# mine.net
KiCad netlist of a schematic drawn in EasyEDA Pro
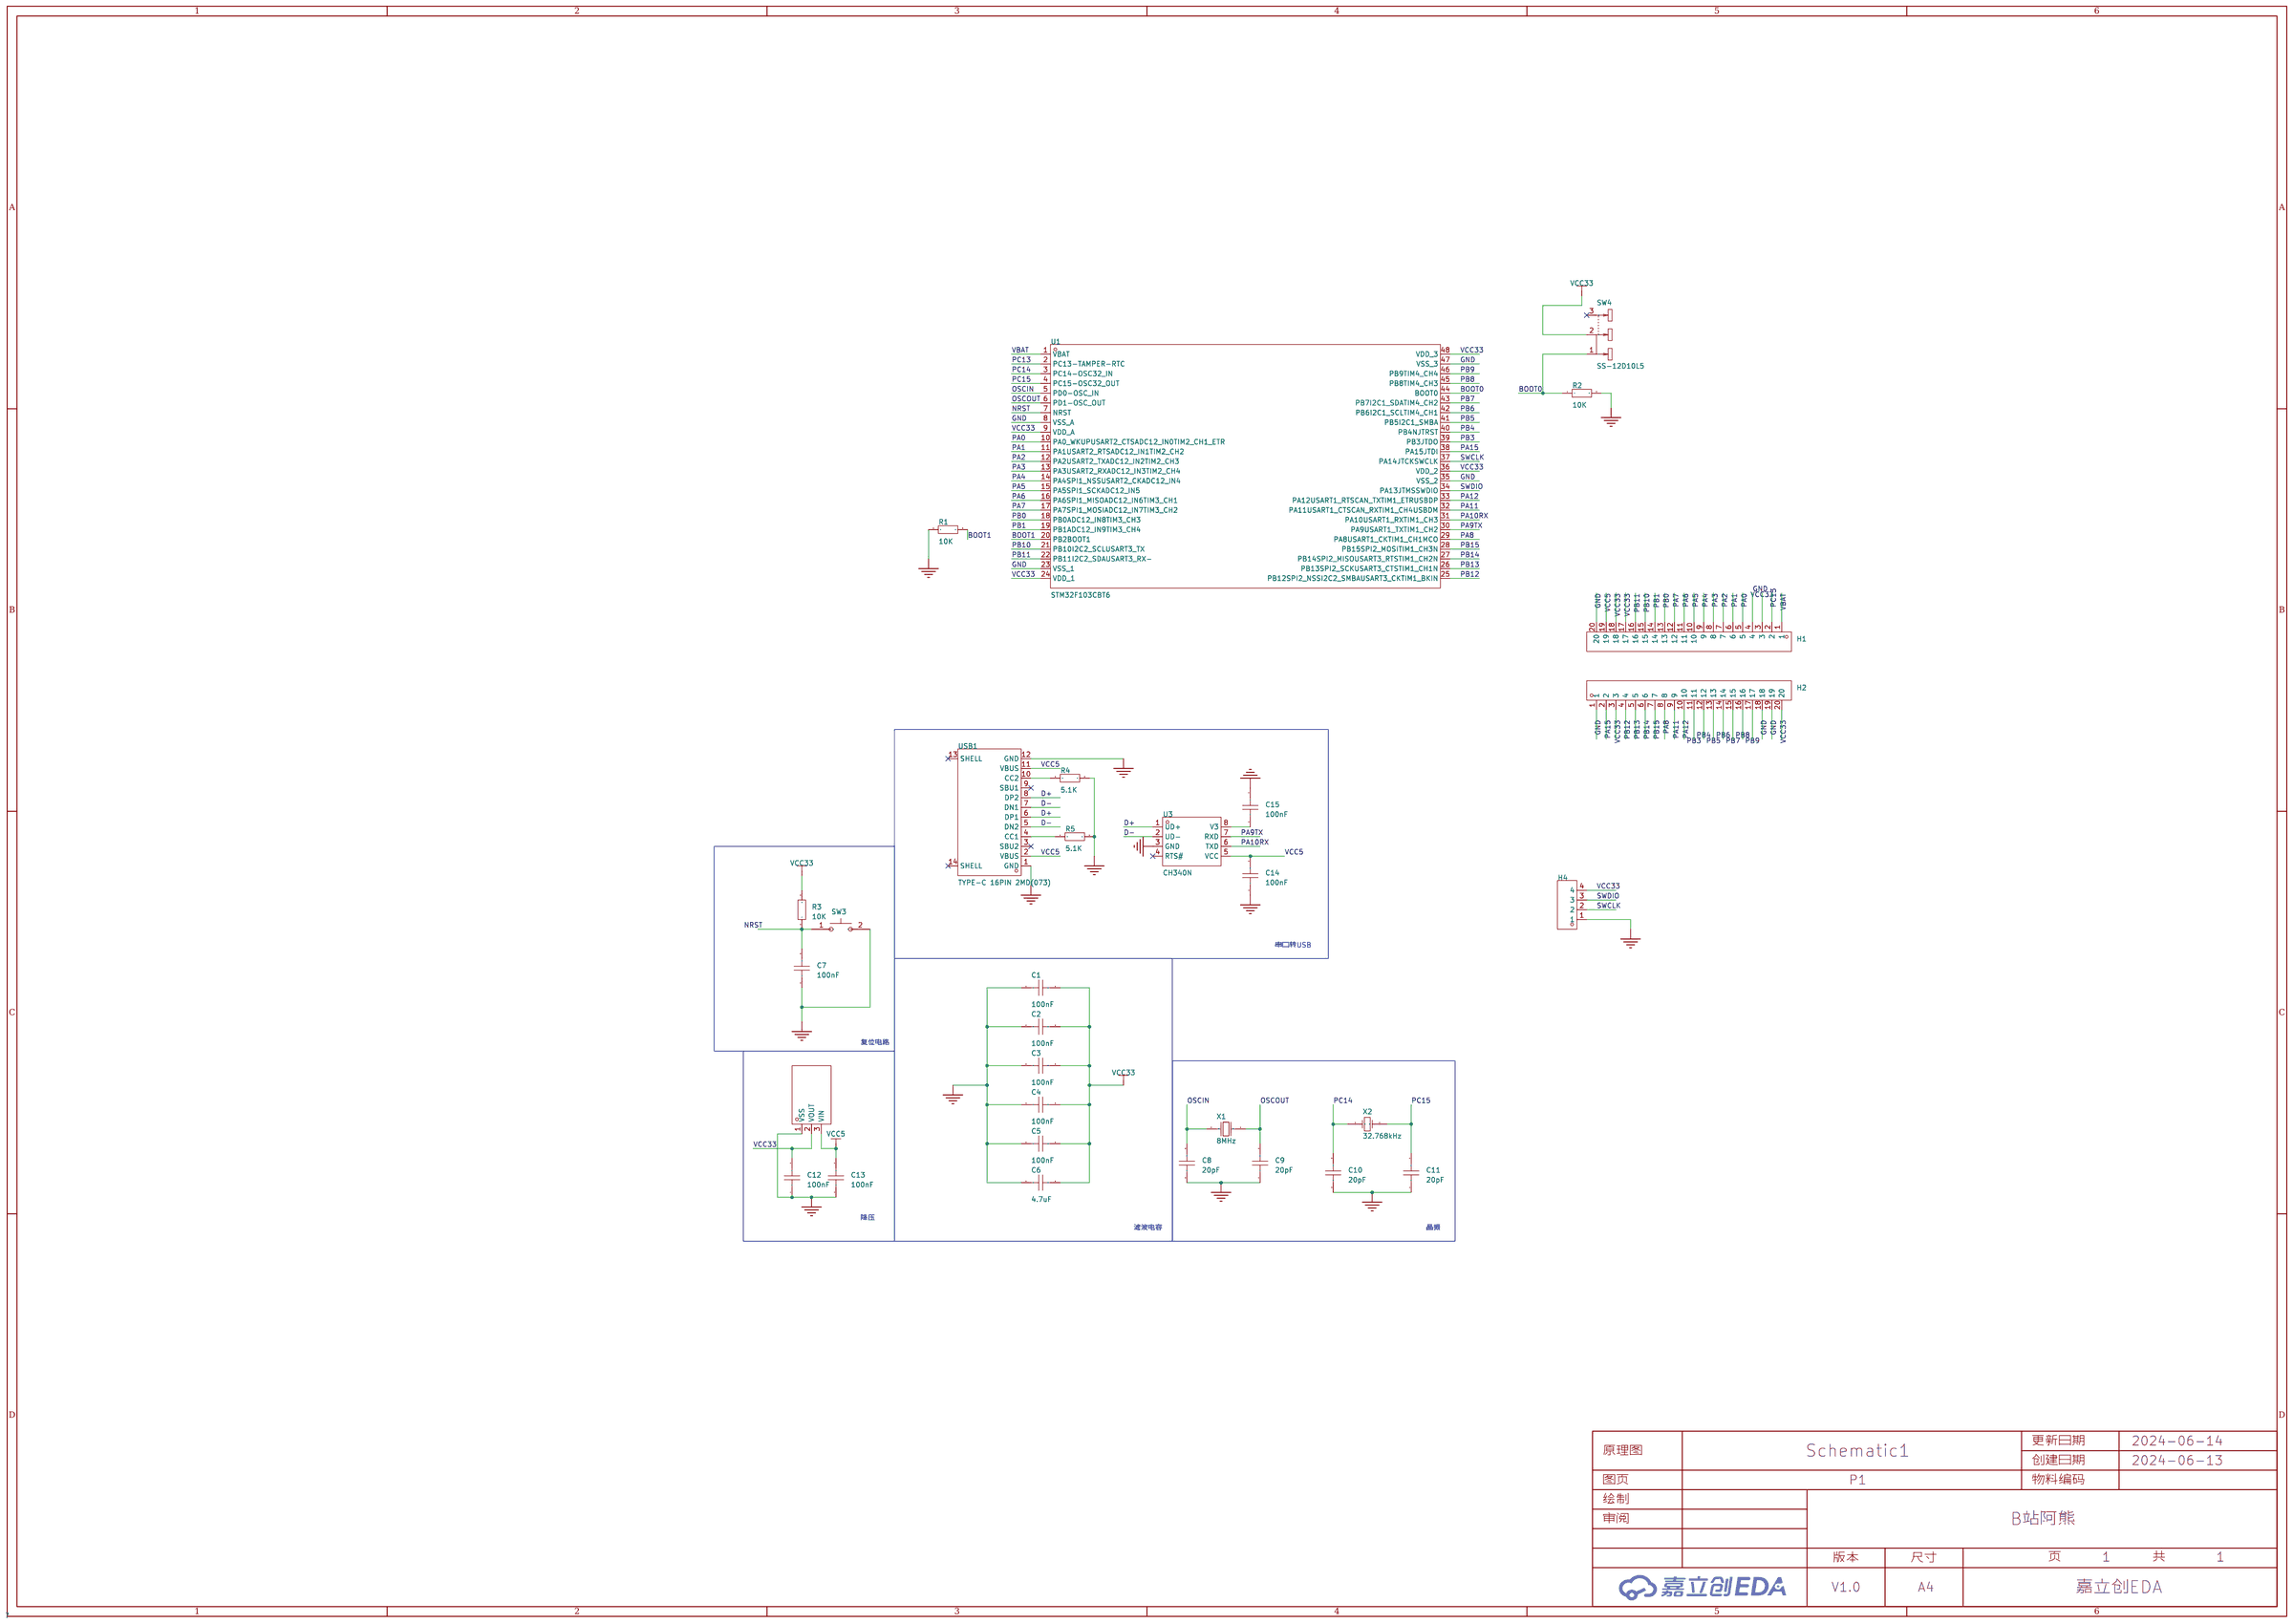
[diagram p0: schematic sheet]

(export (version "E")
  (design (tool "Eeschema 10.0.6"))
  (components
    (comp (ref "C1")
      (value "100nF")
      (footprint "easyedapro:C0603")
      (libsource (lib "easyedapro") (part "CapAcitance"))
    )
    (comp (ref "C2")
      (value "100nF")
      (footprint "easyedapro:C0603")
      (libsource (lib "easyedapro") (part "CapAcitance"))
    )
    (comp (ref "C3")
      (value "100nF")
      (footprint "easyedapro:C0603")
      (libsource (lib "easyedapro") (part "CapAcitance"))
    )
    (comp (ref "C4")
      (value "100nF")
      (footprint "easyedapro:C0603")
      (libsource (lib "easyedapro") (part "CapAcitance"))
    )
    (comp (ref "C5")
      (value "100nF")
      (footprint "easyedapro:C0603")
      (libsource (lib "easyedapro") (part "CapAcitance"))
    )
    (comp (ref "C6")
      (value "4.7uF")
      (footprint "easyedapro:C0603")
      (libsource (lib "easyedapro") (part "CapAcitance"))
    )
    (comp (ref "C7")
      (value "100nF")
      (footprint "easyedapro:C0603")
      (libsource (lib "easyedapro") (part "CapAcitance"))
    )
    (comp (ref "C8")
      (value "20pF")
      (footprint "easyedapro:C0603")
      (libsource (lib "easyedapro") (part "CapAcitance"))
    )
    (comp (ref "C9")
      (value "20pF")
      (footprint "easyedapro:C0603")
      (libsource (lib "easyedapro") (part "CapAcitance"))
    )
    (comp (ref "C10")
      (value "20pF")
      (footprint "easyedapro:C0603")
      (libsource (lib "easyedapro") (part "CapAcitance"))
    )
    (comp (ref "C11")
      (value "20pF")
      (footprint "easyedapro:C0603")
      (libsource (lib "easyedapro") (part "CapAcitance"))
    )
    (comp (ref "C12")
      (value "100nF")
      (footprint "easyedapro:C0603")
      (libsource (lib "easyedapro") (part "CapAcitance"))
    )
    (comp (ref "C13")
      (value "100nF")
      (footprint "easyedapro:C0603")
      (libsource (lib "easyedapro") (part "CapAcitance"))
    )
    (comp (ref "C14")
      (value "100nF")
      (footprint "easyedapro:C0603")
      (libsource (lib "easyedapro") (part "CapAcitance"))
    )
    (comp (ref "C15")
      (value "100nF")
      (footprint "easyedapro:C0603")
      (libsource (lib "easyedapro") (part "CapAcitance"))
    )
    (comp (ref "H1")
      (value "~")
      (footprint "easyedapro:HDR-TH_20P-P2.54-V-M-1")
      (libsource (lib "easyedapro") (part "HDR_2.54-1x20P"))
    )
    (comp (ref "H2")
      (value "~")
      (footprint "easyedapro:HDR-TH_20P-P2.54-V-M-1")
      (libsource (lib "easyedapro") (part "HDR_2.54-1x20P"))
    )
    (comp (ref "H4")
      (value "~")
      (footprint "easyedapro:HDR-TH_4P-P2.54-V-M")
      (libsource (lib "easyedapro") (part "PZ254V-11-04P"))
    )
    (comp (ref "R1") (value "10K") (footprint "easyedapro:R0603") (libsource (lib "easyedapro") (part "电阻")))
    (comp (ref "R2") (value "10K") (footprint "easyedapro:R0603") (libsource (lib "easyedapro") (part "电阻")))
    (comp (ref "R3") (value "10K") (footprint "easyedapro:R0603") (libsource (lib "easyedapro") (part "电阻")))
    (comp (ref "R4") (value "5.1K") (footprint "easyedapro:R0603") (libsource (lib "easyedapro") (part "电阻")))
    (comp (ref "R5") (value "5.1K") (footprint "easyedapro:R0603") (libsource (lib "easyedapro") (part "电阻")))
    (comp (ref "SW3")
      (value "1TS002C-2300-4300-CT")
      (footprint "easyedapro:SW-SMD_L6.0-W3.5-LS8.0-EH")
      (fields (field (name "Manufacturer") "HYP(鸿源精密)"))
      (libsource (lib "easyedapro") (part "1TS002C-2300-4300"))
    )
    (comp (ref "SW4")
      (value "SS-12D10L5")
      (footprint "easyedapro:SW-TH_SS-12D10L5")
      (description "电路结构:单刀双掷;安装方式:直插;开关颜色:黑色;额定电流(DC):3A;额定电压(DC):125V;额定电流(AC):3A;额定电压(AC):125V;机械寿命:1万次;")
      (fields (field (name "Manufacturer") "XKB Connectivity(中国星坤)"))
      (libsource (lib "easyedapro") (part "SS-12D10L5"))
    )
    (comp (ref "U1")
      (value "STM32F103CBT6")
      (footprint "easyedapro:LQFP-48_L7.0-W7.0-P0.50-LS9.0-BL")
      (description "CPU内核:CM3;程序存储容量:128KB;RAM总容量:20KB;GPIO端口数量:37;工作电压范围:2V~3.6V;CPU最大主频:72MHz;程序存储器类型:FLASH;")
      (fields (field (name "Manufacturer") "ST(意法半导体)"))
      (libsource (lib "easyedapro") (part "STM32F103CBT6"))
    )
    (comp (ref "U2")
      (value "ME6206A33XG")
      (footprint "easyedapro:SOT-23-3_L2.9-W1.6-P1.90-LS2.8-BR")
      (description "输出类型:固定;最大输入电压:6V;输出电压:3.3V;最大输出电流:300mA;电源纹波抑制比(PSRR):50dB@(1kHz);输出极性:正极;")
      (fields (field (name "Manufacturer") "MICRONE(南京微盟)"))
      (libsource (lib "easyedapro") (part "ME6206A33XG"))
    )
    (comp (ref "U3")
      (value "CH340N")
      (footprint "easyedapro:SOP-8_L4.9-W3.9-P1.27-LS6.0-BL")
      (fields (field (name "Manufacturer") "WCH(南京沁恒)"))
      (libsource (lib "easyedapro") (part "CH340N_C2977777"))
    )
    (comp (ref "USB1")
      (value "TYPE-C 16PIN 2MD(073)")
      (footprint "easyedapro:USB-C-SMD_TYPE-C-6PIN-2MD-073")
      (description "连接器类型:Type-C;标准:-;公母:母;端口数量:1;触点数量:16P;安装方式:卧贴;额定电流 - 电源:5A;工作温度范围:-25°C~+85°C;")
      (fields (field (name "Manufacturer") "SHOU HAN(首韩)"))
      (libsource (lib "easyedapro") (part "TYPE-C 16PIN 2MD(073)"))
    )
    (comp (ref "X1")
      (value "8MHz")
      (footprint "easyedapro:CRYSTAL-SMD_L11.5-W4.8-LS12.7")
      (description "晶振类型:贴片晶振;频率:8MHz;常温频差:±20ppm;外接负载电容:20pF;频率稳定度(全温):±30ppm;")
      (fields (field (name "Manufacturer Part") "X49SM8MSD2SC") (field (name "Manufacturer") "YXC(扬兴晶振)"))
      (libsource (lib "easyedapro") (part "X49SM8MSD2SC"))
    )
    (comp (ref "X2")
      (value "32.768kHz")
      (footprint "easyedapro:OSC-TH_BD3.1-P0.8-D0.3")
      (description "晶振类型:直插晶振;频率:32.768kHz;常温频差:±10ppm;外接负载电容:12.5pF;频率稳定度(全温):-;")
      (fields (field (name "Manufacturer Part") "X308032768KGB2SC") (field (name "Manufacturer") "YXC(扬兴晶振)"))
      (libsource (lib "easyedapro") (part "X308032768KGB2SC"))
    )
  )
  (nets
    (net (code "1") (name "/BOOT0") (class "Default")
      (node (ref "R2") (pin "1") (pinfunction "1_1") (pintype "input"))
      (node (ref "SW4") (pin "1") (pinfunction "1_1") (pintype "unspecified"))
      (node (ref "U1") (pin "44") (pinfunction "BOOT0_44") (pintype "unspecified"))
    )
    (net (code "2") (name "/BOOT1") (class "Default")
      (node (ref "R1") (pin "2") (pinfunction "2_2") (pintype "input"))
      (node (ref "U1") (pin "20") (pinfunction "PB2BOOT1_20") (pintype "unspecified"))
    )
    (net (code "3") (name "/D+") (class "Default")
      (node (ref "U3") (pin "1") (pinfunction "UD+_1") (pintype "unspecified"))
      (node (ref "USB1") (pin "6") (pinfunction "DP1_6") (pintype "unspecified"))
      (node (ref "USB1") (pin "8") (pinfunction "DP2_8") (pintype "unspecified"))
    )
    (net (code "4") (name "/D-") (class "Default")
      (node (ref "U3") (pin "2") (pinfunction "UD-_2") (pintype "unspecified"))
      (node (ref "USB1") (pin "5") (pinfunction "DN2_5") (pintype "unspecified"))
      (node (ref "USB1") (pin "7") (pinfunction "DN1_7") (pintype "unspecified"))
    )
    (net (code "5") (name "/NRST") (class "Default")
      (node (ref "C7") (pin "2") (pinfunction "2_2") (pintype "input"))
      (node (ref "R3") (pin "1") (pinfunction "1_1") (pintype "input"))
      (node (ref "SW3") (pin "1") (pinfunction "A_1") (pintype "input"))
      (node (ref "U1") (pin "7") (pinfunction "NRST_7") (pintype "unspecified"))
    )
    (net (code "6") (name "/OSCIN") (class "Default")
      (node (ref "C8") (pin "2") (pinfunction "2_2") (pintype "input"))
      (node (ref "U1") (pin "5") (pinfunction "PD0-OSC_IN_5") (pintype "unspecified"))
      (node (ref "X1") (pin "2") (pinfunction "OSC2_2") (pintype "input"))
    )
    (net (code "7") (name "/OSCOUT") (class "Default")
      (node (ref "C9") (pin "2") (pinfunction "2_2") (pintype "input"))
      (node (ref "U1") (pin "6") (pinfunction "PD1-OSC_OUT_6") (pintype "unspecified"))
      (node (ref "X1") (pin "1") (pinfunction "OSC1_1") (pintype "input"))
    )
    (net (code "8") (name "/PA0") (class "Default")
      (node (ref "H1") (pin "5") (pinfunction "5_5") (pintype "input"))
      (node (ref "U1") (pin "10") (pinfunction "PA0_WKUPUSART2_CTSADC12_IN0TIM2_CH1_ETR_10") (pintype "unspecified"))
    )
    (net (code "9") (name "/PA1") (class "Default")
      (node (ref "H1") (pin "6") (pinfunction "6_6") (pintype "input"))
      (node (ref "U1") (pin "11") (pinfunction "PA1USART2_RTSADC12_IN1TIM2_CH2_11") (pintype "unspecified"))
    )
    (net (code "10") (name "/PA2") (class "Default")
      (node (ref "H1") (pin "7") (pinfunction "7_7") (pintype "input"))
      (node (ref "U1") (pin "12") (pinfunction "PA2USART2_TXADC12_IN2TIM2_CH3_12") (pintype "unspecified"))
    )
    (net (code "11") (name "/PA3") (class "Default")
      (node (ref "H1") (pin "8") (pinfunction "8_8") (pintype "input"))
      (node (ref "U1") (pin "13") (pinfunction "PA3USART2_RXADC12_IN3TIM2_CH4_13") (pintype "unspecified"))
    )
    (net (code "12") (name "/PA4") (class "Default")
      (node (ref "H1") (pin "9") (pinfunction "9_9") (pintype "input"))
      (node (ref "U1") (pin "14") (pinfunction "PA4SPI1_NSSUSART2_CKADC12_IN4_14") (pintype "unspecified"))
    )
    (net (code "13") (name "/PA5") (class "Default")
      (node (ref "H1") (pin "10") (pinfunction "10_10") (pintype "input"))
      (node (ref "U1") (pin "15") (pinfunction "PA5SPI1_SCKADC12_IN5_15") (pintype "unspecified"))
    )
    (net (code "14") (name "/PA6") (class "Default")
      (node (ref "H1") (pin "11") (pinfunction "11_11") (pintype "input"))
      (node (ref "U1") (pin "16") (pinfunction "PA6SPI1_MISOADC12_IN6TIM3_CH1_16") (pintype "unspecified"))
    )
    (net (code "15") (name "/PA7") (class "Default")
      (node (ref "H1") (pin "12") (pinfunction "12_12") (pintype "input"))
      (node (ref "U1") (pin "17") (pinfunction "PA7SPI1_MOSIADC12_IN7TIM3_CH2_17") (pintype "unspecified"))
    )
    (net (code "16") (name "/PA8") (class "Default")
      (node (ref "H2") (pin "8") (pinfunction "8_8") (pintype "input"))
      (node (ref "U1") (pin "29") (pinfunction "PA8USART1_CKTIM1_CH1MCO_29") (pintype "unspecified"))
    )
    (net (code "17") (name "/PA9TX") (class "Default")
      (node (ref "U1") (pin "30") (pinfunction "PA9USART1_TXTIM1_CH2_30") (pintype "unspecified"))
      (node (ref "U3") (pin "7") (pinfunction "RXD_7") (pintype "unspecified"))
    )
    (net (code "18") (name "/PA10RX") (class "Default")
      (node (ref "U1") (pin "31") (pinfunction "PA10USART1_RXTIM1_CH3_31") (pintype "unspecified"))
      (node (ref "U3") (pin "6") (pinfunction "TXD_6") (pintype "unspecified"))
    )
    (net (code "19") (name "/PA11") (class "Default")
      (node (ref "H2") (pin "9") (pinfunction "9_9") (pintype "input"))
      (node (ref "U1") (pin "32") (pinfunction "PA11USART1_CTSCAN_RXTIM1_CH4USBDM_32") (pintype "unspecified"))
    )
    (net (code "20") (name "/PA12") (class "Default")
      (node (ref "H2") (pin "10") (pinfunction "10_10") (pintype "input"))
      (node (ref "U1") (pin "33") (pinfunction "PA12USART1_RTSCAN_TXTIM1_ETRUSBDP_33") (pintype "unspecified"))
    )
    (net (code "21") (name "/PA15") (class "Default")
      (node (ref "H2") (pin "2") (pinfunction "2_2") (pintype "input"))
      (node (ref "U1") (pin "38") (pinfunction "PA15JTDI_38") (pintype "unspecified"))
    )
    (net (code "22") (name "/PB0") (class "Default")
      (node (ref "H1") (pin "13") (pinfunction "13_13") (pintype "input"))
      (node (ref "U1") (pin "18") (pinfunction "PB0ADC12_IN8TIM3_CH3_18") (pintype "unspecified"))
    )
    (net (code "23") (name "/PB1") (class "Default")
      (node (ref "H1") (pin "14") (pinfunction "14_14") (pintype "input"))
      (node (ref "U1") (pin "19") (pinfunction "PB1ADC12_IN9TIM3_CH4_19") (pintype "unspecified"))
    )
    (net (code "24") (name "/PB3") (class "Default")
      (node (ref "H2") (pin "11") (pinfunction "11_11") (pintype "input"))
      (node (ref "U1") (pin "39") (pinfunction "PB3JTDO_39") (pintype "unspecified"))
    )
    (net (code "25") (name "/PB4") (class "Default")
      (node (ref "H2") (pin "12") (pinfunction "12_12") (pintype "input"))
      (node (ref "U1") (pin "40") (pinfunction "PB4NJTRST_40") (pintype "unspecified"))
    )
    (net (code "26") (name "/PB5") (class "Default")
      (node (ref "H2") (pin "13") (pinfunction "13_13") (pintype "input"))
      (node (ref "U1") (pin "41") (pinfunction "PB5I2C1_SMBA_41") (pintype "unspecified"))
    )
    (net (code "27") (name "/PB6") (class "Default")
      (node (ref "H2") (pin "14") (pinfunction "14_14") (pintype "input"))
      (node (ref "U1") (pin "42") (pinfunction "PB6I2C1_SCLTIM4_CH1_42") (pintype "unspecified"))
    )
    (net (code "28") (name "/PB7") (class "Default")
      (node (ref "H2") (pin "15") (pinfunction "15_15") (pintype "input"))
      (node (ref "U1") (pin "43") (pinfunction "PB7I2C1_SDATIM4_CH2_43") (pintype "unspecified"))
    )
    (net (code "29") (name "/PB8") (class "Default")
      (node (ref "H2") (pin "16") (pinfunction "16_16") (pintype "input"))
      (node (ref "U1") (pin "45") (pinfunction "PB8TIM4_CH3_45") (pintype "unspecified"))
    )
    (net (code "30") (name "/PB9") (class "Default")
      (node (ref "H2") (pin "17") (pinfunction "17_17") (pintype "input"))
      (node (ref "U1") (pin "46") (pinfunction "PB9TIM4_CH4_46") (pintype "unspecified"))
    )
    (net (code "31") (name "/PB10") (class "Default")
      (node (ref "H1") (pin "15") (pinfunction "15_15") (pintype "input"))
      (node (ref "U1") (pin "21") (pinfunction "PB10I2C2_SCLUSART3_TX_21") (pintype "unspecified"))
    )
    (net (code "32") (name "/PB11") (class "Default")
      (node (ref "H1") (pin "16") (pinfunction "16_16") (pintype "input"))
      (node (ref "U1") (pin "22") (pinfunction "PB11I2C2_SDAUSART3_RX-_22") (pintype "unspecified"))
    )
    (net (code "33") (name "/PB12") (class "Default")
      (node (ref "H2") (pin "4") (pinfunction "4_4") (pintype "input"))
      (node (ref "U1") (pin "25") (pinfunction "PB12SPI2_NSSI2C2_SMBAUSART3_CKTIM1_BKIN_25") (pintype "unspecified"))
    )
    (net (code "34") (name "/PB13") (class "Default")
      (node (ref "H2") (pin "5") (pinfunction "5_5") (pintype "input"))
      (node (ref "U1") (pin "26") (pinfunction "PB13SPI2_SCKUSART3_CTSTIM1_CH1N_26") (pintype "unspecified"))
    )
    (net (code "35") (name "/PB14") (class "Default")
      (node (ref "H2") (pin "6") (pinfunction "6_6") (pintype "input"))
      (node (ref "U1") (pin "27") (pinfunction "PB14SPI2_MISOUSART3_RTSTIM1_CH2N_27") (pintype "unspecified"))
    )
    (net (code "36") (name "/PB15") (class "Default")
      (node (ref "H2") (pin "7") (pinfunction "7_7") (pintype "input"))
      (node (ref "U1") (pin "28") (pinfunction "PB15SPI2_MOSITIM1_CH3N_28") (pintype "unspecified"))
    )
    (net (code "37") (name "/PC13") (class "Default")
      (node (ref "H1") (pin "2") (pinfunction "2_2") (pintype "input"))
      (node (ref "U1") (pin "2") (pinfunction "PC13-TAMPER-RTC_2") (pintype "unspecified"))
    )
    (net (code "38") (name "/PC14") (class "Default")
      (node (ref "C10") (pin "2") (pinfunction "2_2") (pintype "input"))
      (node (ref "U1") (pin "3") (pinfunction "PC14-OSC32_IN_3") (pintype "unspecified"))
      (node (ref "X2") (pin "1") (pinfunction "OSC1_1") (pintype "unspecified"))
    )
    (net (code "39") (name "/PC15") (class "Default")
      (node (ref "C11") (pin "2") (pinfunction "2_2") (pintype "input"))
      (node (ref "U1") (pin "4") (pinfunction "PC15-OSC32_OUT_4") (pintype "unspecified"))
      (node (ref "X2") (pin "2") (pinfunction "OSC2_2") (pintype "unspecified"))
    )
    (net (code "40") (name "/SWCLK") (class "Default")
      (node (ref "H4") (pin "2") (pinfunction "2_2") (pintype "unspecified"))
      (node (ref "U1") (pin "37") (pinfunction "PA14JTCKSWCLK_37") (pintype "unspecified"))
    )
    (net (code "41") (name "/SWDIO") (class "Default")
      (node (ref "H4") (pin "3") (pinfunction "3_3") (pintype "unspecified"))
      (node (ref "U1") (pin "34") (pinfunction "PA13JTMSSWDIO_34") (pintype "unspecified"))
    )
    (net (code "42") (name "/VBAT") (class "Default")
      (node (ref "H1") (pin "1") (pinfunction "1_1") (pintype "input"))
      (node (ref "U1") (pin "1") (pinfunction "VBAT_1") (pintype "unspecified"))
    )
    (net (code "43") (name "GND") (class "Default")
      (node (ref "C1") (pin "1") (pinfunction "1_1") (pintype "input"))
      (node (ref "C10") (pin "1") (pinfunction "1_1") (pintype "input"))
      (node (ref "C11") (pin "1") (pinfunction "1_1") (pintype "input"))
      (node (ref "C12") (pin "1") (pinfunction "1_1") (pintype "input"))
      (node (ref "C13") (pin "1") (pinfunction "1_1") (pintype "input"))
      (node (ref "C14") (pin "1") (pinfunction "1_1") (pintype "input"))
      (node (ref "C15") (pin "1") (pinfunction "1_1") (pintype "input"))
      (node (ref "C2") (pin "1") (pinfunction "1_1") (pintype "input"))
      (node (ref "C3") (pin "1") (pinfunction "1_1") (pintype "input"))
      (node (ref "C4") (pin "1") (pinfunction "1_1") (pintype "input"))
      (node (ref "C5") (pin "1") (pinfunction "1_1") (pintype "input"))
      (node (ref "C6") (pin "1") (pinfunction "1_1") (pintype "input"))
      (node (ref "C7") (pin "1") (pinfunction "1_1") (pintype "input"))
      (node (ref "C8") (pin "1") (pinfunction "1_1") (pintype "input"))
      (node (ref "C9") (pin "1") (pinfunction "1_1") (pintype "input"))
      (node (ref "H1") (pin "20") (pinfunction "20_20") (pintype "input"))
      (node (ref "H1") (pin "4") (pinfunction "4_4") (pintype "input"))
      (node (ref "H2") (pin "1") (pinfunction "1_1") (pintype "input"))
      (node (ref "H2") (pin "18") (pinfunction "18_18") (pintype "input"))
      (node (ref "H2") (pin "19") (pinfunction "19_19") (pintype "input"))
      (node (ref "H4") (pin "1") (pinfunction "1_1") (pintype "unspecified"))
      (node (ref "R1") (pin "1") (pinfunction "1_1") (pintype "input"))
      (node (ref "R2") (pin "2") (pinfunction "2_2") (pintype "input"))
      (node (ref "R4") (pin "2") (pinfunction "2_2") (pintype "input"))
      (node (ref "R5") (pin "2") (pinfunction "2_2") (pintype "input"))
      (node (ref "SW3") (pin "2") (pinfunction "B_2") (pintype "input"))
      (node (ref "U1") (pin "23") (pinfunction "VSS_1_23") (pintype "unspecified"))
      (node (ref "U1") (pin "35") (pinfunction "VSS_2_35") (pintype "unspecified"))
      (node (ref "U1") (pin "47") (pinfunction "VSS_3_47") (pintype "unspecified"))
      (node (ref "U1") (pin "8") (pinfunction "VSS_A_8") (pintype "unspecified"))
      (node (ref "U2") (pin "1") (pinfunction "VSS_1") (pintype "input"))
      (node (ref "U3") (pin "3") (pinfunction "GND_3") (pintype "unspecified"))
      (node (ref "USB1") (pin "1") (pinfunction "GND_1") (pintype "unspecified"))
      (node (ref "USB1") (pin "12") (pinfunction "GND_12") (pintype "unspecified"))
    )
    (net (code "44") (name "Net-(U3-V3)") (class "Default")
      (node (ref "C15") (pin "2") (pinfunction "2_2") (pintype "input"))
      (node (ref "U3") (pin "8") (pinfunction "V3_8") (pintype "unspecified"))
    )
    (net (code "45") (name "Net-(USB1-CC1)") (class "Default")
      (node (ref "R5") (pin "1") (pinfunction "1_1") (pintype "input"))
      (node (ref "USB1") (pin "4") (pinfunction "CC1_4") (pintype "unspecified"))
    )
    (net (code "46") (name "Net-(USB1-CC2)") (class "Default")
      (node (ref "R4") (pin "1") (pinfunction "1_1") (pintype "input"))
      (node (ref "USB1") (pin "10") (pinfunction "CC2_10") (pintype "unspecified"))
    )
    (net (code "47") (name "VCC5") (class "Default")
      (node (ref "C13") (pin "2") (pinfunction "2_2") (pintype "input"))
      (node (ref "C14") (pin "2") (pinfunction "2_2") (pintype "input"))
      (node (ref "H1") (pin "19") (pinfunction "19_19") (pintype "input"))
      (node (ref "U2") (pin "3") (pinfunction "VIN_3") (pintype "input"))
      (node (ref "U3") (pin "5") (pinfunction "VCC_5") (pintype "unspecified"))
      (node (ref "USB1") (pin "11") (pinfunction "VBUS_11") (pintype "unspecified"))
      (node (ref "USB1") (pin "2") (pinfunction "VBUS_2") (pintype "unspecified"))
    )
    (net (code "48") (name "VCC33") (class "Default")
      (node (ref "C1") (pin "2") (pinfunction "2_2") (pintype "input"))
      (node (ref "C12") (pin "2") (pinfunction "2_2") (pintype "input"))
      (node (ref "C2") (pin "2") (pinfunction "2_2") (pintype "input"))
      (node (ref "C3") (pin "2") (pinfunction "2_2") (pintype "input"))
      (node (ref "C4") (pin "2") (pinfunction "2_2") (pintype "input"))
      (node (ref "C5") (pin "2") (pinfunction "2_2") (pintype "input"))
      (node (ref "C6") (pin "2") (pinfunction "2_2") (pintype "input"))
      (node (ref "H1") (pin "17") (pinfunction "17_17") (pintype "input"))
      (node (ref "H1") (pin "18") (pinfunction "18_18") (pintype "input"))
      (node (ref "H1") (pin "3") (pinfunction "3_3") (pintype "input"))
      (node (ref "H2") (pin "20") (pinfunction "20_20") (pintype "input"))
      (node (ref "H2") (pin "3") (pinfunction "3_3") (pintype "input"))
      (node (ref "H4") (pin "4") (pinfunction "4_4") (pintype "unspecified"))
      (node (ref "R3") (pin "2") (pinfunction "2_2") (pintype "input"))
      (node (ref "SW4") (pin "2") (pinfunction "2_2") (pintype "unspecified"))
      (node (ref "U1") (pin "24") (pinfunction "VDD_1_24") (pintype "unspecified"))
      (node (ref "U1") (pin "36") (pinfunction "VDD_2_36") (pintype "unspecified"))
      (node (ref "U1") (pin "48") (pinfunction "VDD_3_48") (pintype "unspecified"))
      (node (ref "U1") (pin "9") (pinfunction "VDD_A_9") (pintype "unspecified"))
      (node (ref "U2") (pin "2") (pinfunction "VOUT_2") (pintype "input"))
    )
    (net (code "49") (name "unconnected-(SW4-Pad3)") (class "Default")
      (node (ref "SW4") (pin "3") (pinfunction "3_3") (pintype "unspecified+no_connect"))
    )
    (net (code "50") (name "unconnected-(U3-RTS#-Pad4)") (class "Default")
      (node (ref "U3") (pin "4") (pinfunction "RTS#_4") (pintype "unspecified+no_connect"))
    )
    (net (code "51") (name "unconnected-(USB1-SBU1-Pad9)") (class "Default")
      (node (ref "USB1") (pin "9") (pinfunction "SBU1_9") (pintype "unspecified+no_connect"))
    )
    (net (code "52") (name "unconnected-(USB1-SBU2-Pad3)") (class "Default")
      (node (ref "USB1") (pin "3") (pinfunction "SBU2_3") (pintype "unspecified+no_connect"))
    )
    (net (code "53") (name "unconnected-(USB1-SHELL-Pad13)") (class "Default")
      (node (ref "USB1") (pin "13") (pinfunction "SHELL_13") (pintype "unspecified+no_connect"))
    )
    (net (code "54") (name "unconnected-(USB1-SHELL-Pad14)") (class "Default")
      (node (ref "USB1") (pin "14") (pinfunction "SHELL_14") (pintype "unspecified+no_connect"))
    )
  )
)
